# opamp.net
KiCad netlist of a schematic drawn in EAGLE
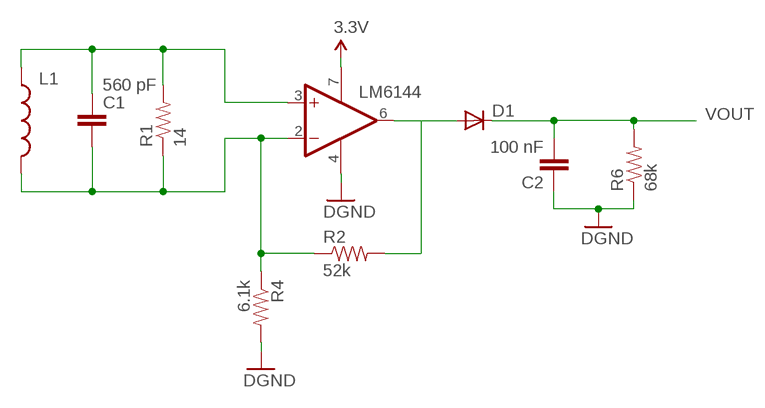
[diagram p0: schematic, sheet 1]

(export (version "E")
  (design (tool "Eeschema 10.0.6"))
  (components
    (comp (ref "C1")
      (value "560 pF")
      (footprint "eagle-import:0603-CAP")
      (libsource (lib "eagle-import") (part "CAP0603-CAP"))
    )
    (comp (ref "C2")
      (value "100 nF")
      (footprint "eagle-import:0603-CAP")
      (libsource (lib "eagle-import") (part "CAP0603-CAP"))
    )
    (comp (ref "D1")
      (value "DIODE1N4148")
      (footprint "eagle-import:DIODE-1N4148")
      (libsource (lib "eagle-import") (part "DIODE1N4148"))
    )
    (comp (ref "L1")
      (value "INDUCTOR-")
      (footprint "eagle-import:CDRH3D28")
      (libsource (lib "eagle-import") (part "INDUCTOR-"))
    )
    (comp (ref "LM6144")
      (value "1AMP_P7+4N")
      (footprint "eagle-import:DIL08")
      (libsource (lib "eagle-import") (part "1AMP_P7+4N"))
    )
    (comp (ref "R1")
      (value "14")
      (footprint "eagle-import:0603-RES")
      (libsource (lib "eagle-import") (part "RESISTOR0603-RES"))
    )
    (comp (ref "R2")
      (value "52k")
      (footprint "eagle-import:0805")
      (libsource (lib "eagle-import") (part "RESISTOR0805-RES"))
    )
    (comp (ref "R4")
      (value "6.1k")
      (footprint "eagle-import:0805")
      (libsource (lib "eagle-import") (part "RESISTOR0805-RES"))
    )
    (comp (ref "R6")
      (value "68k")
      (footprint "eagle-import:0805")
      (libsource (lib "eagle-import") (part "RESISTOR0805-RES"))
    )
  )
  (nets
    (net (code "1") (name "/VOUT") (class "Default")
      (node (ref "C2") (pin "2") (pinfunction "2_2") (pintype "passive"))
      (node (ref "D1") (pin "C") (pinfunction "C_C") (pintype "passive"))
      (node (ref "R6") (pin "2") (pinfunction "2_2") (pintype "passive"))
    )
    (net (code "2") (name "3.3V") (class "Default")
      (node (ref "LM6144") (pin "7") (pinfunction "V+_7") (pintype "power_in"))
    )
    (net (code "3") (name "DGND") (class "Default")
      (node (ref "C2") (pin "1") (pinfunction "1_1") (pintype "passive"))
      (node (ref "LM6144") (pin "4") (pinfunction "V-_4") (pintype "power_in"))
      (node (ref "R4") (pin "2") (pinfunction "2_2") (pintype "passive"))
      (node (ref "R6") (pin "1") (pinfunction "1_1") (pintype "passive"))
    )
    (net (code "4") (name "Net-(LM6144-+IN)") (class "Default")
      (node (ref "C1") (pin "1") (pinfunction "1_1") (pintype "passive"))
      (node (ref "L1") (pin "1") (pinfunction "1_1") (pintype "passive"))
      (node (ref "LM6144") (pin "3") (pinfunction "+IN_3") (pintype "input"))
      (node (ref "R1") (pin "2") (pinfunction "2_2") (pintype "passive"))
    )
    (net (code "5") (name "Net-(LM6144--IN)") (class "Default")
      (node (ref "C1") (pin "2") (pinfunction "2_2") (pintype "passive"))
      (node (ref "L1") (pin "2") (pinfunction "2_2") (pintype "passive"))
      (node (ref "LM6144") (pin "2") (pinfunction "-IN_2") (pintype "input"))
      (node (ref "R1") (pin "1") (pinfunction "1_1") (pintype "passive"))
      (node (ref "R2") (pin "1") (pinfunction "1_1") (pintype "passive"))
      (node (ref "R4") (pin "1") (pinfunction "1_1") (pintype "passive"))
    )
    (net (code "6") (name "Net-(LM6144-OUT)") (class "Default")
      (node (ref "D1") (pin "A") (pinfunction "A_A") (pintype "passive"))
      (node (ref "LM6144") (pin "6") (pinfunction "OUT_6") (pintype "output"))
      (node (ref "R2") (pin "2") (pinfunction "2_2") (pintype "passive"))
    )
  )
)
